# button.net
KiCad netlist of a schematic drawn in Altium Designer
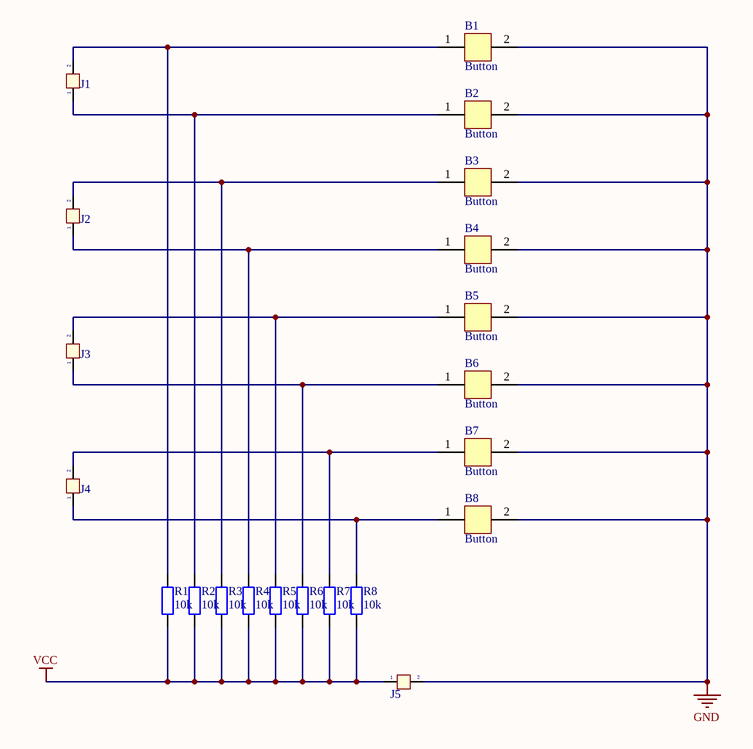
[diagram p0: button.SchDoc]

(export (version "E")
  (design (tool "Eeschema 10.0.6"))
  (components
    (comp (ref "B1")
      (value "Button")
      (footprint "Button 2 Pin")
      (description "Button 2 pin")
      (libsource (lib "Cty1") (part "Button 2 Pin"))
    )
    (comp (ref "B2")
      (value "Button")
      (footprint "Button 2 Pin")
      (description "Button 2 pin")
      (libsource (lib "Cty1") (part "Button 2 Pin"))
    )
    (comp (ref "B3")
      (value "Button")
      (footprint "Button 2 Pin")
      (description "Button 2 pin")
      (libsource (lib "Cty1") (part "Button 2 Pin"))
    )
    (comp (ref "B4")
      (value "Button")
      (footprint "Button 2 Pin")
      (description "Button 2 pin")
      (libsource (lib "Cty1") (part "Button 2 Pin"))
    )
    (comp (ref "B5")
      (value "Button")
      (footprint "Button 2 Pin")
      (description "Button 2 pin")
      (libsource (lib "Cty1") (part "Button 2 Pin"))
    )
    (comp (ref "B6")
      (value "Button")
      (footprint "Button 2 Pin")
      (description "Button 2 pin")
      (libsource (lib "Cty1") (part "Button 2 Pin"))
    )
    (comp (ref "B7")
      (value "Button")
      (footprint "Button 2 Pin")
      (description "Button 2 pin")
      (libsource (lib "Cty1") (part "Button 2 Pin"))
    )
    (comp (ref "B8")
      (value "Button")
      (footprint "Button 2 Pin")
      (description "Button 2 pin")
      (libsource (lib "Cty1") (part "Button 2 Pin"))
    )
    (comp (ref "J1") (value "Jumper 2") (footprint "JP2") (libsource (lib "Cty1") (part "JP 2")))
    (comp (ref "J2") (value "Jumper 2") (footprint "JP2") (libsource (lib "Cty1") (part "JP 2")))
    (comp (ref "J3") (value "Jumper 2") (footprint "JP2") (libsource (lib "Cty1") (part "JP 2")))
    (comp (ref "J4") (value "Jumper 2") (footprint "JP2") (libsource (lib "Cty1") (part "JP 2")))
    (comp (ref "J5") (value "Jumper 2") (footprint "JP2") (libsource (lib "") (part "JP 2_1")))
    (comp (ref "R1")
      (value "10k")
      (footprint "R1/4W")
      (description "Resistor 1/4W")
      (libsource (lib "syhaunguyen") (part "R1/4W"))
    )
    (comp (ref "R2")
      (value "10k")
      (footprint "R1/4W")
      (description "Resistor 1/4W")
      (libsource (lib "syhaunguyen") (part "R1/4W"))
    )
    (comp (ref "R3")
      (value "10k")
      (footprint "R1/4W")
      (description "Resistor 1/4W")
      (libsource (lib "syhaunguyen") (part "R1/4W"))
    )
    (comp (ref "R4")
      (value "10k")
      (footprint "R1/4W")
      (description "Resistor 1/4W")
      (libsource (lib "syhaunguyen") (part "R1/4W"))
    )
    (comp (ref "R5")
      (value "10k")
      (footprint "R1/4W")
      (description "Resistor 1/4W")
      (libsource (lib "syhaunguyen") (part "R1/4W"))
    )
    (comp (ref "R6")
      (value "10k")
      (footprint "R1/4W")
      (description "Resistor 1/4W")
      (libsource (lib "syhaunguyen") (part "R1/4W"))
    )
    (comp (ref "R7")
      (value "10k")
      (footprint "R1/4W")
      (description "Resistor 1/4W")
      (libsource (lib "syhaunguyen") (part "R1/4W"))
    )
    (comp (ref "R8")
      (value "10k")
      (footprint "R1/4W")
      (description "Resistor 1/4W")
      (libsource (lib "syhaunguyen") (part "R1/4W"))
    )
  )
  (nets
    (net (code "1") (name "GND") (class "Default")
      (node (ref "B1") (pin "2") (pinfunction "2_2") (pintype "passive"))
      (node (ref "B2") (pin "2") (pinfunction "2_2") (pintype "passive"))
      (node (ref "B3") (pin "2") (pinfunction "2_2") (pintype "passive"))
      (node (ref "B4") (pin "2") (pinfunction "2_2") (pintype "passive"))
      (node (ref "B5") (pin "2") (pinfunction "2_2") (pintype "passive"))
      (node (ref "B6") (pin "2") (pinfunction "2_2") (pintype "passive"))
      (node (ref "B7") (pin "2") (pinfunction "2_2") (pintype "passive"))
      (node (ref "B8") (pin "2") (pinfunction "2_2") (pintype "passive"))
      (node (ref "J5") (pin "2") (pinfunction "2_2") (pintype "passive"))
    )
    (net (code "2") (name "Net-(B1-Pad1)") (class "Default")
      (node (ref "B1") (pin "1") (pinfunction "1_1") (pintype "passive"))
      (node (ref "J1") (pin "2") (pinfunction "2_2") (pintype "passive"))
      (node (ref "R1") (pin "2") (pinfunction "2_2") (pintype "passive"))
    )
    (net (code "3") (name "Net-(B2-Pad1)") (class "Default")
      (node (ref "B2") (pin "1") (pinfunction "1_1") (pintype "passive"))
      (node (ref "J1") (pin "1") (pinfunction "1_1") (pintype "passive"))
      (node (ref "R2") (pin "2") (pinfunction "2_2") (pintype "passive"))
    )
    (net (code "4") (name "Net-(B3-Pad1)") (class "Default")
      (node (ref "B3") (pin "1") (pinfunction "1_1") (pintype "passive"))
      (node (ref "J2") (pin "2") (pinfunction "2_2") (pintype "passive"))
      (node (ref "R3") (pin "2") (pinfunction "2_2") (pintype "passive"))
    )
    (net (code "5") (name "Net-(B4-Pad1)") (class "Default")
      (node (ref "B4") (pin "1") (pinfunction "1_1") (pintype "passive"))
      (node (ref "J2") (pin "1") (pinfunction "1_1") (pintype "passive"))
      (node (ref "R4") (pin "2") (pinfunction "2_2") (pintype "passive"))
    )
    (net (code "6") (name "Net-(B5-Pad1)") (class "Default")
      (node (ref "B5") (pin "1") (pinfunction "1_1") (pintype "passive"))
      (node (ref "J3") (pin "2") (pinfunction "2_2") (pintype "passive"))
      (node (ref "R5") (pin "2") (pinfunction "2_2") (pintype "passive"))
    )
    (net (code "7") (name "Net-(B6-Pad1)") (class "Default")
      (node (ref "B6") (pin "1") (pinfunction "1_1") (pintype "passive"))
      (node (ref "J3") (pin "1") (pinfunction "1_1") (pintype "passive"))
      (node (ref "R6") (pin "2") (pinfunction "2_2") (pintype "passive"))
    )
    (net (code "8") (name "Net-(B7-Pad1)") (class "Default")
      (node (ref "B7") (pin "1") (pinfunction "1_1") (pintype "passive"))
      (node (ref "J4") (pin "2") (pinfunction "2_2") (pintype "passive"))
      (node (ref "R7") (pin "2") (pinfunction "2_2") (pintype "passive"))
    )
    (net (code "9") (name "Net-(B8-Pad1)") (class "Default")
      (node (ref "B8") (pin "1") (pinfunction "1_1") (pintype "passive"))
      (node (ref "J4") (pin "1") (pinfunction "1_1") (pintype "passive"))
      (node (ref "R8") (pin "2") (pinfunction "2_2") (pintype "passive"))
    )
    (net (code "10") (name "VCC") (class "Default")
      (node (ref "J5") (pin "1") (pinfunction "1_1") (pintype "passive"))
      (node (ref "R1") (pin "1") (pinfunction "1_1") (pintype "passive"))
      (node (ref "R2") (pin "1") (pinfunction "1_1") (pintype "passive"))
      (node (ref "R3") (pin "1") (pinfunction "1_1") (pintype "passive"))
      (node (ref "R4") (pin "1") (pinfunction "1_1") (pintype "passive"))
      (node (ref "R5") (pin "1") (pinfunction "1_1") (pintype "passive"))
      (node (ref "R6") (pin "1") (pinfunction "1_1") (pintype "passive"))
      (node (ref "R7") (pin "1") (pinfunction "1_1") (pintype "passive"))
      (node (ref "R8") (pin "1") (pinfunction "1_1") (pintype "passive"))
    )
  )
)
